# Schematic_TuYa_led_driver.net
KiCad netlist of a schematic drawn in EasyEDA
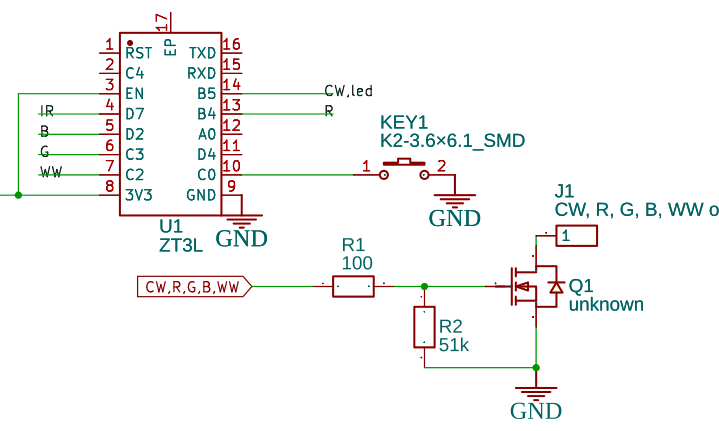
[diagram p0: schematic sheet]

(export (version "E")
  (design (tool "Eeschema 10.0.6"))
  (components
    (comp (ref "J1")
      (value "CW, R, G, B, WW out")
      (fields (field (name "BOM_Supplier Part") "C81276"))
      (libsource (lib "") (part "HDR-M-2.54_1x1"))
    )
    (comp (ref "KEY1")
      (value "K2-3.6×6.1_SMD")
      (fields
        (field (name "BOM_Manufacturer Part") "K2-1107ST-A4SW-06")
        (field (name "BOM_Supplier Part") "C118141")
      )
      (libsource (lib "") (part "K2-3.6×6.1_SMD"))
    )
    (comp (ref "Q1")
      (value "unknown")
      (fields (field (name "BOM_Manufacturer Part") "2N7002,215") (field (name "BOM_Supplier Part") "C65189"))
      (libsource (lib "") (part "2N7002"))
    )
    (comp (ref "R1") (value "100") (libsource (lib "") (part "R_0603_EU")))
    (comp (ref "R2") (value "51k") (libsource (lib "") (part "R_0603_EU_1")))
    (comp (ref "U1")
      (value "ZT3L")
      (fields (field (name "BOM_Supplier Part") "C2897596"))
      (libsource (lib "") (part "ZT3L"))
    )
  )
  (nets
    (net (code "1") (name "/B") (class "Default")
      (node (ref "U1") (pin "5") (pinfunction "D2_5") (pintype "unspecified"))
    )
    (net (code "2") (name "/CW,led") (class "Default")
      (node (ref "U1") (pin "14") (pinfunction "B5_14") (pintype "unspecified"))
    )
    (net (code "3") (name "/G") (class "Default")
      (node (ref "U1") (pin "6") (pinfunction "C3_6") (pintype "unspecified"))
    )
    (net (code "4") (name "/IR") (class "Default")
      (node (ref "U1") (pin "4") (pinfunction "D7_4") (pintype "unspecified"))
    )
    (net (code "5") (name "/R") (class "Default")
      (node (ref "U1") (pin "13") (pinfunction "B4_13") (pintype "unspecified"))
    )
    (net (code "6") (name "/WW") (class "Default")
      (node (ref "U1") (pin "7") (pinfunction "C2_7") (pintype "unspecified"))
    )
    (net (code "7") (name "3.3V") (class "Default")
      (node (ref "U1") (pin "3") (pinfunction "EN_3") (pintype "unspecified"))
      (node (ref "U1") (pin "8") (pinfunction "3V3_8") (pintype "unspecified"))
    )
    (net (code "8") (name "CW,R,G,B,WW") (class "Default")
      (node (ref "R1") (pin "1") (pinfunction "1_1") (pintype "unspecified"))
    )
    (net (code "9") (name "GND") (class "Default")
      (node (ref "KEY1") (pin "2") (pinfunction "2_2") (pintype "unspecified"))
      (node (ref "Q1") (pin "2") (pinfunction "S_2") (pintype "unspecified"))
      (node (ref "R2") (pin "2") (pinfunction "2_2") (pintype "unspecified"))
      (node (ref "U1") (pin "9") (pinfunction "GND_9") (pintype "unspecified"))
    )
    (net (code "10") (name "Net-(Q1-D)") (class "Default")
      (node (ref "J1") (pin "1") (pinfunction "1_1") (pintype "input"))
      (node (ref "Q1") (pin "3") (pinfunction "D_3") (pintype "unspecified"))
    )
    (net (code "11") (name "Net-(Q1-G)") (class "Default")
      (node (ref "Q1") (pin "1") (pinfunction "G_1") (pintype "unspecified"))
      (node (ref "R1") (pin "2") (pinfunction "2_2") (pintype "unspecified"))
      (node (ref "R2") (pin "1") (pinfunction "1_1") (pintype "unspecified"))
    )
    (net (code "12") (name "Net-(U1-C0)") (class "Default")
      (node (ref "KEY1") (pin "1") (pinfunction "1_1") (pintype "unspecified"))
      (node (ref "U1") (pin "10") (pinfunction "C0_10") (pintype "unspecified"))
    )
    (net (code "13") (name "unconnected-(U1-A0-Pad12)") (class "Default")
      (node (ref "U1") (pin "12") (pinfunction "A0_12") (pintype "unspecified"))
    )
    (net (code "14") (name "unconnected-(U1-C4-Pad2)") (class "Default")
      (node (ref "U1") (pin "2") (pinfunction "C4_2") (pintype "unspecified"))
    )
    (net (code "15") (name "unconnected-(U1-D4-Pad11)") (class "Default")
      (node (ref "U1") (pin "11") (pinfunction "D4_11") (pintype "unspecified"))
    )
    (net (code "16") (name "unconnected-(U1-EP-Pad17)") (class "Default")
      (node (ref "U1") (pin "17") (pinfunction "EP_17") (pintype "unspecified"))
    )
    (net (code "17") (name "unconnected-(U1-RST-Pad1)") (class "Default")
      (node (ref "U1") (pin "1") (pinfunction "RST_1") (pintype "unspecified"))
    )
    (net (code "18") (name "unconnected-(U1-RXD-Pad15)") (class "Default")
      (node (ref "U1") (pin "15") (pinfunction "RXD_15") (pintype "unspecified"))
    )
    (net (code "19") (name "unconnected-(U1-TXD-Pad16)") (class "Default")
      (node (ref "U1") (pin "16") (pinfunction "TXD_16") (pintype "unspecified"))
    )
  )
)
